# Sheet1.net
KiCad netlist of a schematic drawn in Altium Designer
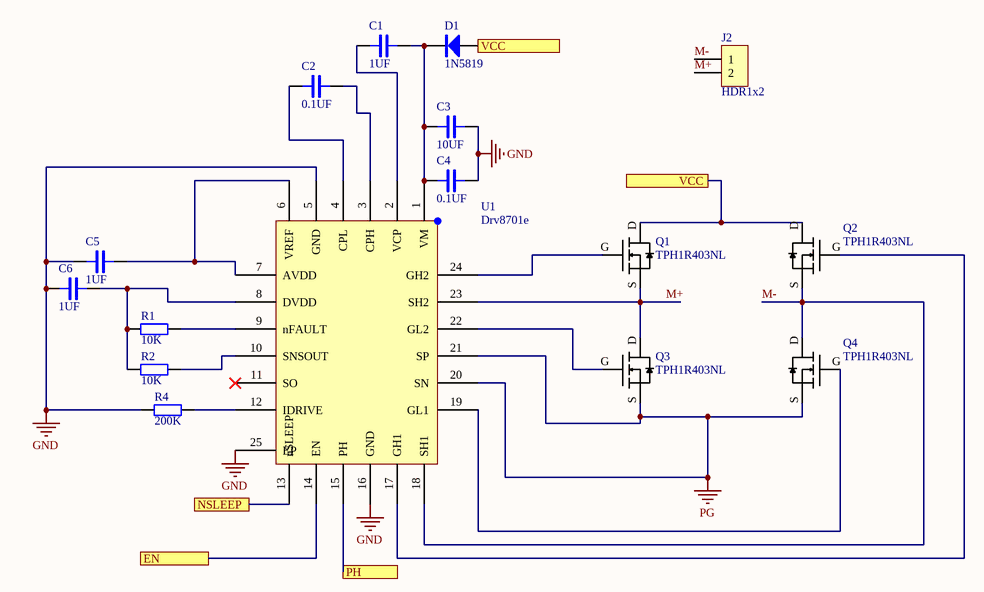
[diagram p0: Sheet1.SchDoc]

(export (version "E")
  (design (tool "Eeschema 10.0.6"))
  (components
    (comp (ref "C1")
      (value "1UF")
      (footprint "0603")
      (description "Capacitor")
      (libsource (lib "General") (part "CAP"))
    )
    (comp (ref "C2")
      (value "0.1UF")
      (footprint "0603")
      (description "Capacitor")
      (libsource (lib "General") (part "CAP"))
    )
    (comp (ref "C3")
      (value "10UF")
      (footprint "0603")
      (description "Capacitor")
      (libsource (lib "General") (part "CAP"))
    )
    (comp (ref "C4")
      (value "0.1UF")
      (footprint "0603")
      (description "Capacitor")
      (libsource (lib "General") (part "CAP"))
    )
    (comp (ref "C5")
      (value "1UF")
      (footprint "0603")
      (description "Capacitor")
      (libsource (lib "General") (part "CAP"))
    )
    (comp (ref "C6")
      (value "1UF")
      (footprint "0603")
      (description "Capacitor")
      (libsource (lib "General") (part "CAP"))
    )
    (comp (ref "D1")
      (value "1N5819")
      (footprint "SOD-123")
      (description "高速开关二极管")
      (fields (field (name "版权归属") "源创客"))
      (libsource (lib "二极管-整流桥") (part "1N4148"))
    )
    (comp (ref "J2")
      (value "HDR1x2")
      (footprint "TX30_接口")
      (description "Connector")
      (libsource (lib "General") (part "HDR1x2"))
    )
    (comp (ref "Q1")
      (value "TPH1R403NL")
      (footprint "TPH1R403NL")
      (libsource (lib "General") (part "TPH1R403NL"))
    )
    (comp (ref "Q2")
      (value "TPH1R403NL")
      (footprint "TPH1R403NL")
      (libsource (lib "General") (part "TPH1R403NL"))
    )
    (comp (ref "Q3")
      (value "TPH1R403NL")
      (footprint "TPH1R403NL")
      (libsource (lib "General") (part "TPH1R403NL"))
    )
    (comp (ref "Q4")
      (value "TPH1R403NL")
      (footprint "TPH1R403NL")
      (libsource (lib "General") (part "TPH1R403NL"))
    )
    (comp (ref "R1")
      (value "10K")
      (footprint "0603")
      (description "Resistor")
      (libsource (lib "General") (part "RES"))
    )
    (comp (ref "R2")
      (value "10K")
      (footprint "0603")
      (description "Resistor")
      (libsource (lib "General") (part "RES"))
    )
    (comp (ref "R4")
      (value "200K")
      (footprint "0603")
      (description "Resistor")
      (libsource (lib "General") (part "RES"))
    )
    (comp (ref "U1") (value "Drv8701e") (footprint "DRV8701E") (libsource (lib "General") (part "Drv8701e")))
  )
  (nets
    (net (code "1") (name "/EN") (class "Default")
      (node (ref "U1") (pin "14") (pinfunction "EN_14") (pintype "passive"))
    )
    (net (code "2") (name "/M+") (class "Default")
      (node (ref "J2") (pin "2") (pinfunction "2_2") (pintype "passive"))
      (node (ref "Q1") (pin "S") (pinfunction "S_S") (pintype "passive"))
      (node (ref "Q3") (pin "D") (pinfunction "D_D") (pintype "passive"))
      (node (ref "U1") (pin "23") (pinfunction "SH2_23") (pintype "passive"))
    )
    (net (code "3") (name "/M-") (class "Default")
      (node (ref "J2") (pin "1") (pinfunction "1_1") (pintype "passive"))
      (node (ref "Q2") (pin "S") (pinfunction "S_S") (pintype "passive"))
      (node (ref "Q4") (pin "D") (pinfunction "D_D") (pintype "passive"))
      (node (ref "U1") (pin "18") (pinfunction "SH1_18") (pintype "passive"))
    )
    (net (code "4") (name "/NSLEEP") (class "Default")
      (node (ref "U1") (pin "13") (pinfunction "nSLEEP_13") (pintype "passive"))
    )
    (net (code "5") (name "/PH") (class "Default")
      (node (ref "U1") (pin "15") (pinfunction "PH_15") (pintype "passive"))
    )
    (net (code "6") (name "/VCC") (class "Default")
      (node (ref "D1") (pin "1") (pinfunction "A_1") (pintype "passive"))
      (node (ref "Q1") (pin "D") (pinfunction "D_D") (pintype "passive"))
      (node (ref "Q2") (pin "D") (pinfunction "D_D") (pintype "passive"))
    )
    (net (code "7") (name "GND") (class "Default")
      (node (ref "C3") (pin "2") (pinfunction "2_2") (pintype "passive"))
      (node (ref "C4") (pin "2") (pinfunction "2_2") (pintype "passive"))
      (node (ref "C5") (pin "1") (pinfunction "1_1") (pintype "passive"))
      (node (ref "C6") (pin "1") (pinfunction "1_1") (pintype "passive"))
      (node (ref "R4") (pin "2") (pinfunction "2_2") (pintype "passive"))
      (node (ref "U1") (pin "16") (pinfunction "GND_16") (pintype "passive"))
      (node (ref "U1") (pin "25") (pinfunction "EP_25") (pintype "passive"))
      (node (ref "U1") (pin "5") (pinfunction "GND_5") (pintype "passive"))
    )
    (net (code "8") (name "Net-(D1-K)") (class "Default")
      (node (ref "C1") (pin "2") (pinfunction "2_2") (pintype "passive"))
      (node (ref "C3") (pin "1") (pinfunction "1_1") (pintype "passive"))
      (node (ref "C4") (pin "1") (pinfunction "1_1") (pintype "passive"))
      (node (ref "D1") (pin "2") (pinfunction "K_2") (pintype "passive"))
      (node (ref "U1") (pin "1") (pinfunction "VM_1") (pintype "passive"))
    )
    (net (code "9") (name "Net-(U1-AVDD)") (class "Default")
      (node (ref "C5") (pin "2") (pinfunction "2_2") (pintype "passive"))
      (node (ref "U1") (pin "6") (pinfunction "VREF_6") (pintype "passive"))
      (node (ref "U1") (pin "7") (pinfunction "AVDD_7") (pintype "passive"))
    )
    (net (code "10") (name "Net-(U1-CPH)") (class "Default")
      (node (ref "C2") (pin "2") (pinfunction "2_2") (pintype "passive"))
      (node (ref "U1") (pin "3") (pinfunction "CPH_3") (pintype "passive"))
    )
    (net (code "11") (name "Net-(U1-CPL)") (class "Default")
      (node (ref "C2") (pin "1") (pinfunction "1_1") (pintype "passive"))
      (node (ref "U1") (pin "4") (pinfunction "CPL_4") (pintype "passive"))
    )
    (net (code "12") (name "Net-(U1-DVDD)") (class "Default")
      (node (ref "C6") (pin "2") (pinfunction "2_2") (pintype "passive"))
      (node (ref "R1") (pin "2") (pinfunction "2_2") (pintype "passive"))
      (node (ref "R2") (pin "2") (pinfunction "2_2") (pintype "passive"))
      (node (ref "U1") (pin "8") (pinfunction "DVDD_8") (pintype "passive"))
    )
    (net (code "13") (name "Net-(U1-GH1)") (class "Default")
      (node (ref "Q2") (pin "G") (pinfunction "S_G") (pintype "passive"))
      (node (ref "U1") (pin "17") (pinfunction "GH1_17") (pintype "passive"))
    )
    (net (code "14") (name "Net-(U1-GH2)") (class "Default")
      (node (ref "Q1") (pin "G") (pinfunction "S_G") (pintype "passive"))
      (node (ref "U1") (pin "24") (pinfunction "GH2_24") (pintype "passive"))
    )
    (net (code "15") (name "Net-(U1-GL1)") (class "Default")
      (node (ref "Q4") (pin "G") (pinfunction "S_G") (pintype "passive"))
      (node (ref "U1") (pin "19") (pinfunction "GL1_19") (pintype "passive"))
    )
    (net (code "16") (name "Net-(U1-GL2)") (class "Default")
      (node (ref "Q3") (pin "G") (pinfunction "S_G") (pintype "passive"))
      (node (ref "U1") (pin "22") (pinfunction "GL2_22") (pintype "passive"))
    )
    (net (code "17") (name "Net-(U1-IDRIVE)") (class "Default")
      (node (ref "R4") (pin "1") (pinfunction "1_1") (pintype "passive"))
      (node (ref "U1") (pin "12") (pinfunction "IDRIVE_12") (pintype "passive"))
    )
    (net (code "18") (name "Net-(U1-SNSOUT)") (class "Default")
      (node (ref "R2") (pin "1") (pinfunction "1_1") (pintype "passive"))
      (node (ref "U1") (pin "10") (pinfunction "SNSOUT_10") (pintype "passive"))
    )
    (net (code "19") (name "Net-(U1-VCP)") (class "Default")
      (node (ref "C1") (pin "1") (pinfunction "1_1") (pintype "passive"))
      (node (ref "U1") (pin "2") (pinfunction "VCP_2") (pintype "passive"))
    )
    (net (code "20") (name "Net-(U1-nFAULT)") (class "Default")
      (node (ref "R1") (pin "1") (pinfunction "1_1") (pintype "passive"))
      (node (ref "U1") (pin "9") (pinfunction "nFAULT_9") (pintype "passive"))
    )
    (net (code "21") (name "PG") (class "Default")
      (node (ref "Q3") (pin "S") (pinfunction "S_S") (pintype "passive"))
      (node (ref "Q4") (pin "S") (pinfunction "S_S") (pintype "passive"))
      (node (ref "U1") (pin "20") (pinfunction "SN_20") (pintype "passive"))
      (node (ref "U1") (pin "21") (pinfunction "SP_21") (pintype "passive"))
    )
    (net (code "22") (name "unconnected-(U1-SO-Pad11)") (class "Default")
      (node (ref "U1") (pin "11") (pinfunction "SO_11") (pintype "passive+no_connect"))
    )
  )
)
